# output.net
KiCad netlist of a schematic drawn in EAGLE
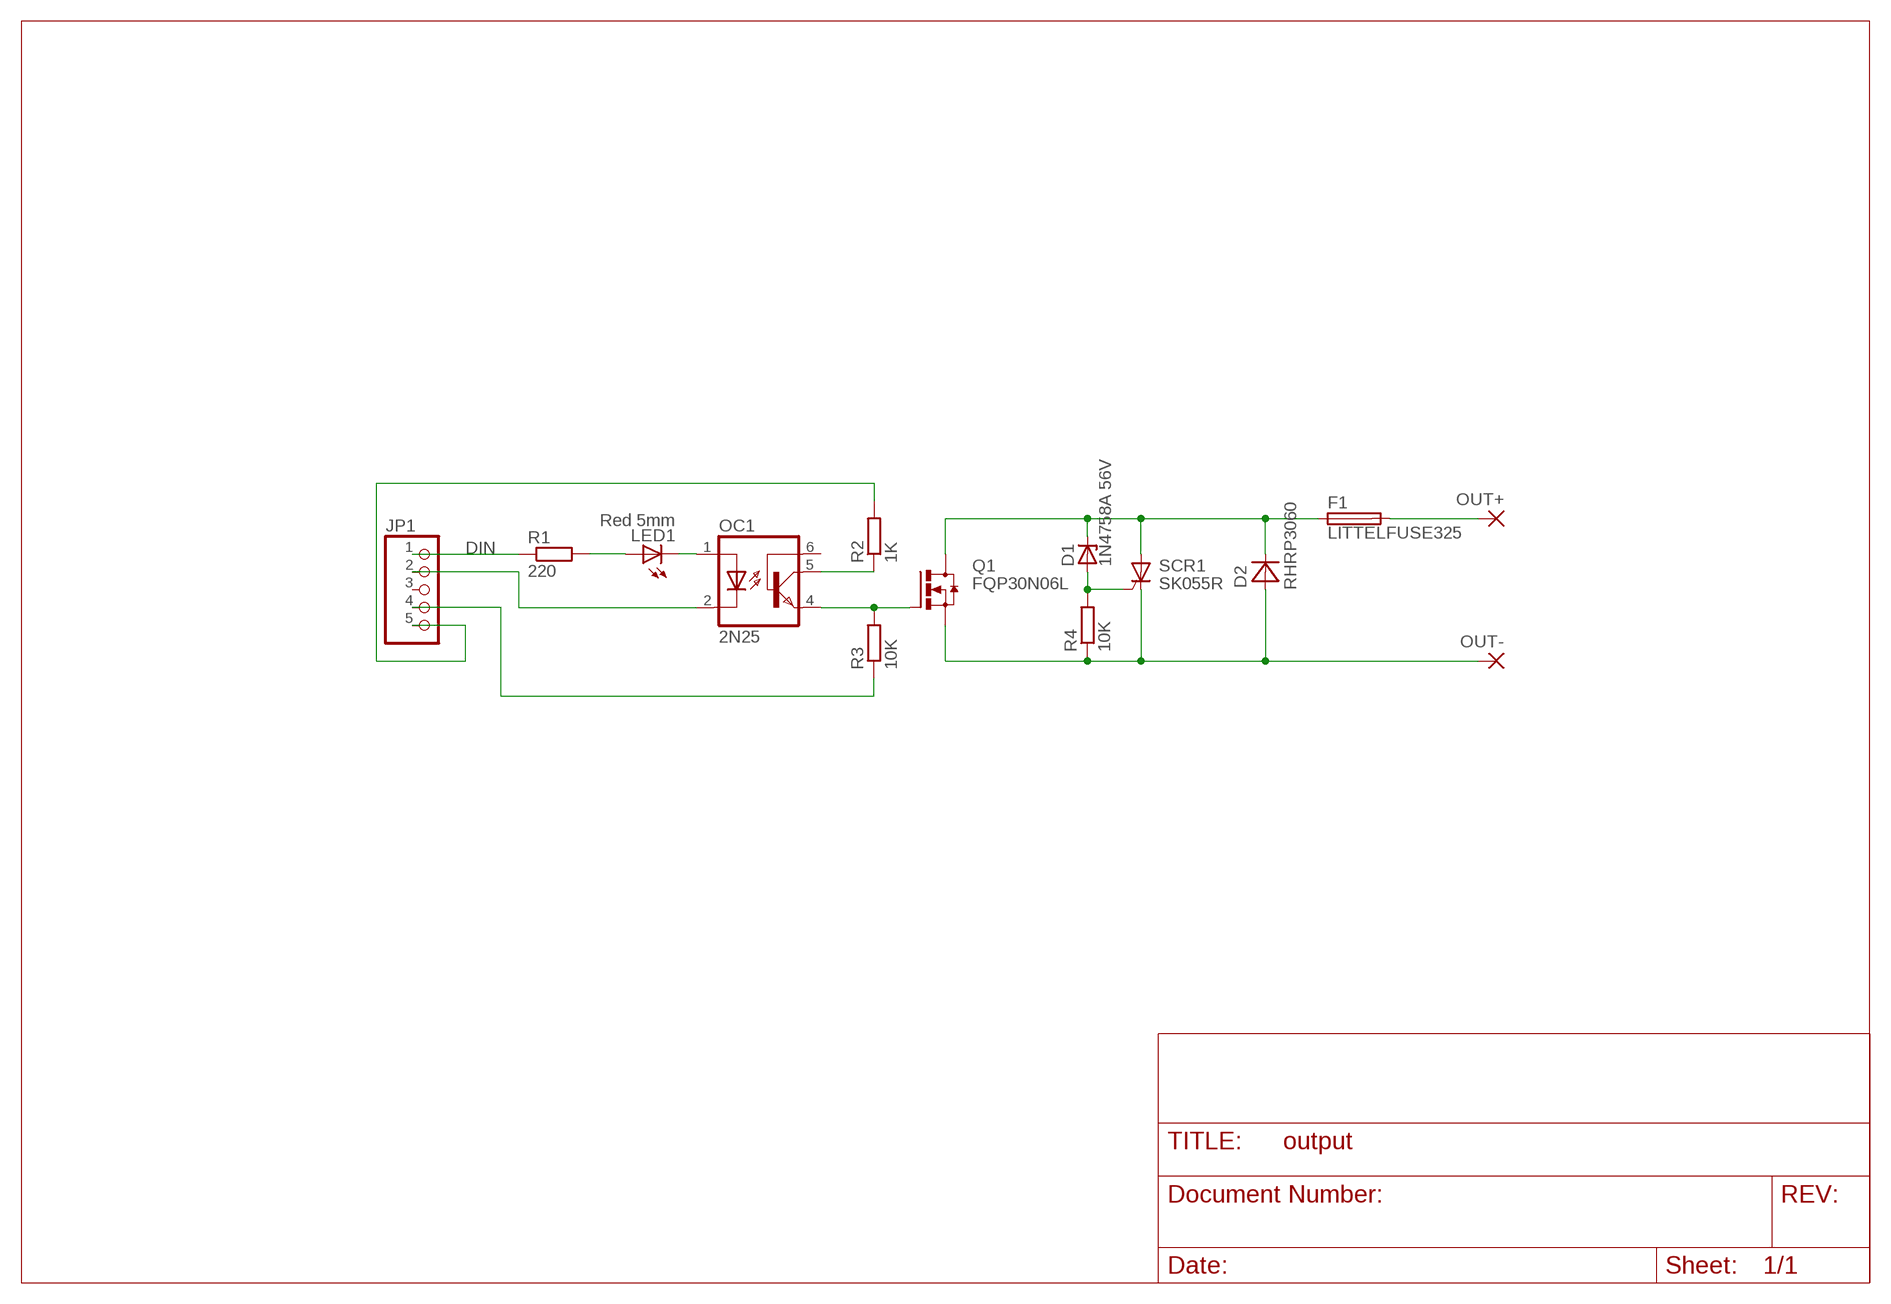
[diagram p0: schematic, sheet 1]

(export (version "E")
  (design (tool "Eeschema 10.0.6"))
  (components
    (comp (ref "D1")
      (value "1N4758A 56V")
      (footprint "eagle-import:DO41Z10")
      (libsource (lib "eagle-import") (part "ZENER-DIODEDO41Z10"))
    )
    (comp (ref "D2")
      (value "RHRP3060")
      (footprint "eagle-import:TO-220CAS-HS")
      (libsource (lib "eagle-import") (part "RHRP3060HEATSINK"))
    )
    (comp (ref "F1")
      (value "LITTELFUSE325")
      (footprint "eagle-import:LITTELFUSE-325")
      (libsource (lib "eagle-import") (part "LITTELFUSE325"))
    )
    (comp (ref "JP1")
      (value "PINHD-1X5")
      (footprint "eagle-import:1X05")
      (libsource (lib "eagle-import") (part "PINHD-1X5"))
    )
    (comp (ref "LED1")
      (value "Red 5mm")
      (footprint "eagle-import:LED5MM")
      (libsource (lib "eagle-import") (part "LED5MM"))
    )
    (comp (ref "OC1")
      (value "2N25")
      (footprint "eagle-import:DIL-06")
      (libsource (lib "eagle-import") (part "2N25"))
    )
    (comp (ref "OUT+")
      (value "2,54/1,1")
      (footprint "eagle-import:2,54_1,1")
      (libsource (lib "eagle-import") (part "2,54/1,1"))
    )
    (comp (ref "OUT-")
      (value "2,54/1,1")
      (footprint "eagle-import:2,54_1,1")
      (libsource (lib "eagle-import") (part "2,54/1,1"))
    )
    (comp (ref "Q1")
      (value "FQP30N06L")
      (footprint "eagle-import:TO-220BV-HS")
      (libsource (lib "eagle-import") (part "FQP30N06LHEATSINK"))
    )
    (comp (ref "R1")
      (value "220")
      (footprint "eagle-import:0207_10")
      (libsource (lib "eagle-import") (part "R-EU_0207/10"))
    )
    (comp (ref "R2")
      (value "1K")
      (footprint "eagle-import:0207_10")
      (libsource (lib "eagle-import") (part "R-EU_0207/10"))
    )
    (comp (ref "R3")
      (value "10K")
      (footprint "eagle-import:0207_10")
      (libsource (lib "eagle-import") (part "R-EU_0207/10"))
    )
    (comp (ref "R4")
      (value "10K")
      (footprint "eagle-import:0207_10")
      (libsource (lib "eagle-import") (part "R-EU_0207/10"))
    )
    (comp (ref "SCR1")
      (value "SK055R")
      (footprint "eagle-import:TO-220V-HS")
      (libsource (lib "eagle-import") (part "SK055RHEATSINK"))
    )
  )
  (nets
    (net (code "1") (name "/DIN") (class "Default")
      (node (ref "JP1") (pin "1") (pinfunction "1_1") (pintype "passive"))
      (node (ref "R1") (pin "1") (pinfunction "1_1") (pintype "passive"))
    )
    (net (code "2") (name "Net-(F1-1)") (class "Default")
      (node (ref "D1") (pin "C") (pinfunction "C_C") (pintype "passive"))
      (node (ref "D2") (pin "C") (pinfunction "C_C") (pintype "passive"))
      (node (ref "F1") (pin "P$1") (pinfunction "1_P$1") (pintype "passive"))
      (node (ref "Q1") (pin "D") (pinfunction "D_D") (pintype "passive"))
      (node (ref "SCR1") (pin "2") (pinfunction "A_2") (pintype "passive"))
    )
    (net (code "3") (name "Net-(F1-2)") (class "Default")
      (node (ref "F1") (pin "P$2") (pinfunction "2_P$2") (pintype "passive"))
      (node (ref "OUT+") (pin "1") (pinfunction "P_1") (pintype "passive"))
    )
    (net (code "4") (name "Net-(JP1-Pad4)") (class "Default")
      (node (ref "JP1") (pin "4") (pinfunction "4_4") (pintype "passive"))
      (node (ref "R3") (pin "1") (pinfunction "1_1") (pintype "passive"))
    )
    (net (code "5") (name "Net-(JP1-Pad5)") (class "Default")
      (node (ref "JP1") (pin "5") (pinfunction "5_5") (pintype "passive"))
      (node (ref "R2") (pin "2") (pinfunction "2_2") (pintype "passive"))
    )
    (net (code "6") (name "Net-(LED1-C)") (class "Default")
      (node (ref "LED1") (pin "K") (pinfunction "C_K") (pintype "passive"))
      (node (ref "OC1") (pin "1") (pinfunction "A_1") (pintype "passive"))
    )
    (net (code "7") (name "Net-(LED1-PadA)") (class "Default")
      (node (ref "LED1") (pin "A") (pinfunction "A_A") (pintype "passive"))
      (node (ref "R1") (pin "2") (pinfunction "2_2") (pintype "passive"))
    )
    (net (code "8") (name "Net-(OC1-C)") (class "Default")
      (node (ref "JP1") (pin "2") (pinfunction "2_2") (pintype "passive"))
      (node (ref "OC1") (pin "2") (pinfunction "C_2") (pintype "passive"))
    )
    (net (code "9") (name "Net-(OC1-COL)") (class "Default")
      (node (ref "OC1") (pin "5") (pinfunction "COL_5") (pintype "passive"))
      (node (ref "R2") (pin "1") (pinfunction "1_1") (pintype "passive"))
    )
    (net (code "10") (name "Net-(OC1-EMI)") (class "Default")
      (node (ref "OC1") (pin "4") (pinfunction "EMI_4") (pintype "passive"))
      (node (ref "Q1") (pin "G") (pinfunction "G_G") (pintype "passive"))
      (node (ref "R3") (pin "2") (pinfunction "2_2") (pintype "passive"))
    )
    (net (code "11") (name "Net-(OUT--P)") (class "Default")
      (node (ref "D2") (pin "A") (pinfunction "A_A") (pintype "passive"))
      (node (ref "OUT-") (pin "1") (pinfunction "P_1") (pintype "passive"))
      (node (ref "Q1") (pin "S") (pinfunction "S_S") (pintype "passive"))
      (node (ref "R4") (pin "1") (pinfunction "1_1") (pintype "passive"))
      (node (ref "SCR1") (pin "1") (pinfunction "C_1") (pintype "passive"))
    )
    (net (code "12") (name "Net-(SCR1-G)") (class "Default")
      (node (ref "D1") (pin "A") (pinfunction "A_A") (pintype "passive"))
      (node (ref "R4") (pin "2") (pinfunction "2_2") (pintype "passive"))
      (node (ref "SCR1") (pin "3") (pinfunction "G_3") (pintype "passive"))
    )
    (net (code "13") (name "unconnected-(JP1-Pad3)") (class "Default")
      (node (ref "JP1") (pin "3") (pinfunction "3_3") (pintype "passive"))
    )
    (net (code "14") (name "unconnected-(OC1-BAS-Pad6)") (class "Default")
      (node (ref "OC1") (pin "6") (pinfunction "BAS_6") (pintype "passive"))
    )
  )
)
